# RcTransmitterSwitches.net
KiCad netlist of a schematic drawn in Altium Designer
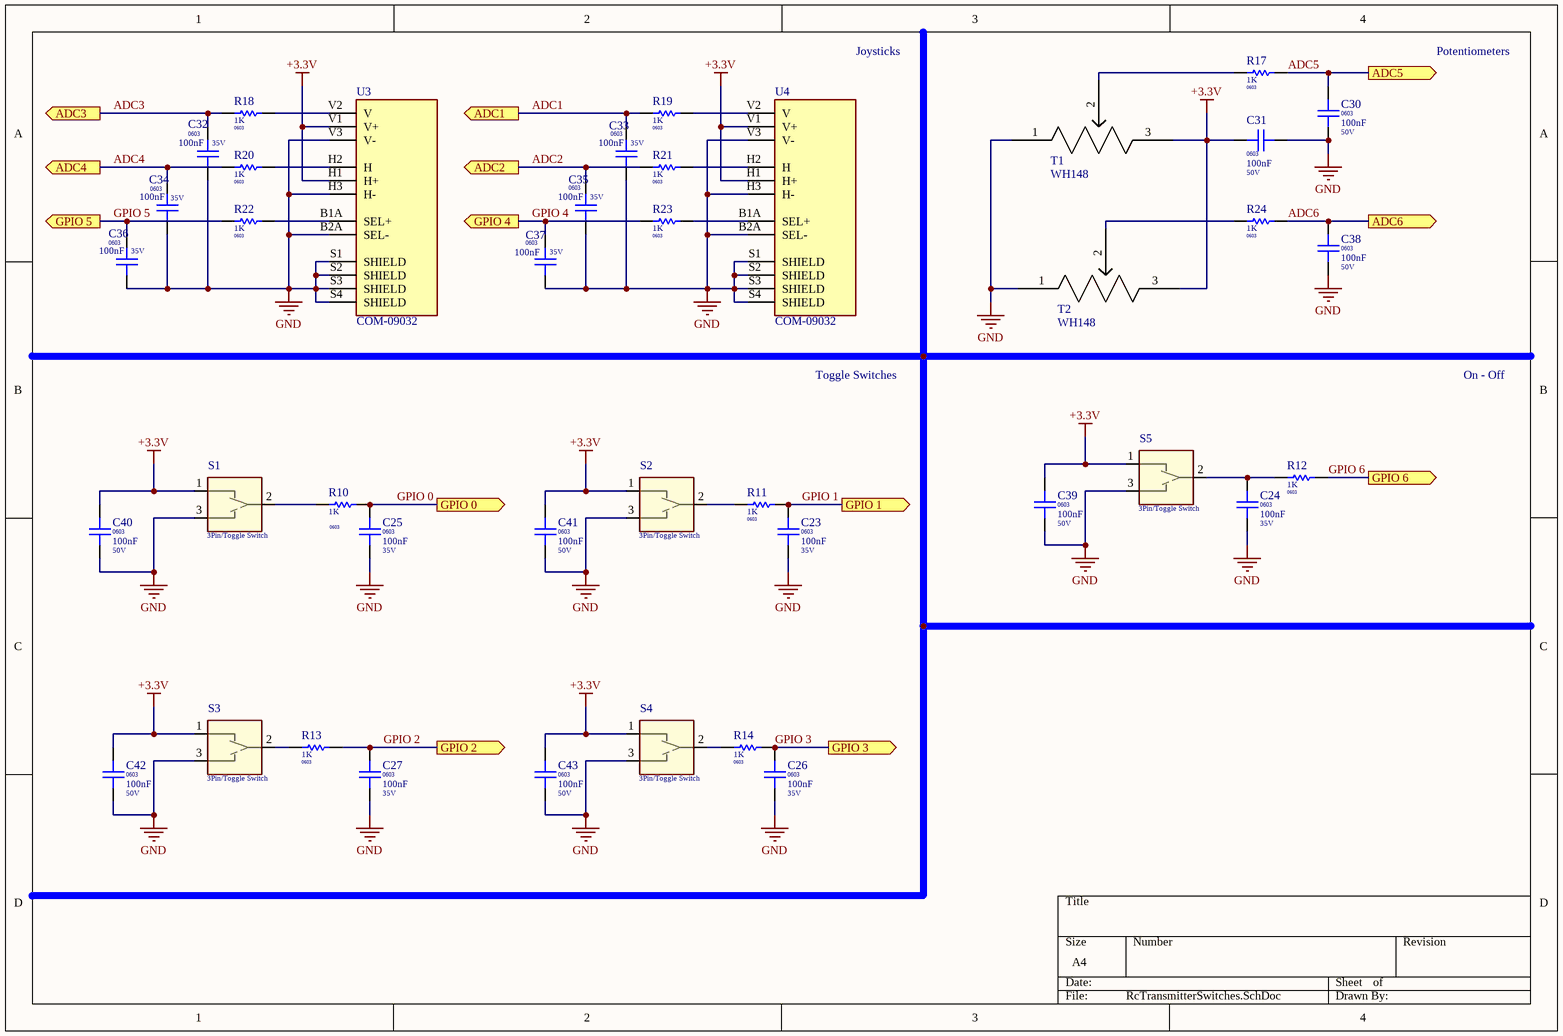
[diagram p0: RcTransmitterSwitches.SchDoc]

(export (version "E")
  (design (tool "Eeschema 10.0.6"))
  (components
    (comp (ref "C23")
      (value "100nF")
      (footprint "CAPC 0603")
      (description "Capacitor Ceramic 100nF 35V 0603")
      (fields
        (field (name "TOLERANCE") "%10")
        (field (name "PACKAGE / CASE") "0603")
        (field (name "VOLTAGE") "35V")
        (field (name "PART NUMBER") "CAPC0328")
      )
      (libsource (lib "AESK Database Library") (part "NPCapacitor"))
    )
    (comp (ref "C24")
      (value "100nF")
      (footprint "CAPC 0603")
      (description "Capacitor Ceramic 100nF 35V 0603")
      (fields
        (field (name "TOLERANCE") "%10")
        (field (name "PACKAGE / CASE") "0603")
        (field (name "VOLTAGE") "35V")
        (field (name "PART NUMBER") "CAPC0328")
      )
      (libsource (lib "AESK Database Library") (part "NPCapacitor"))
    )
    (comp (ref "C25")
      (value "100nF")
      (footprint "CAPC 0603")
      (description "Capacitor Ceramic 100nF 35V 0603")
      (fields
        (field (name "TOLERANCE") "%10")
        (field (name "PACKAGE / CASE") "0603")
        (field (name "VOLTAGE") "35V")
        (field (name "PART NUMBER") "CAPC0328")
      )
      (libsource (lib "AESK Database Library") (part "NPCapacitor"))
    )
    (comp (ref "C26")
      (value "100nF")
      (footprint "CAPC 0603")
      (description "Capacitor Ceramic 100nF 35V 0603")
      (fields
        (field (name "TOLERANCE") "%10")
        (field (name "PACKAGE / CASE") "0603")
        (field (name "VOLTAGE") "35V")
        (field (name "PART NUMBER") "CAPC0328")
      )
      (libsource (lib "AESK Database Library") (part "NPCapacitor"))
    )
    (comp (ref "C27")
      (value "100nF")
      (footprint "CAPC 0603")
      (description "Capacitor Ceramic 100nF 35V 0603")
      (fields
        (field (name "TOLERANCE") "%10")
        (field (name "PACKAGE / CASE") "0603")
        (field (name "VOLTAGE") "35V")
        (field (name "PART NUMBER") "CAPC0328")
      )
      (libsource (lib "AESK Database Library") (part "NPCapacitor"))
    )
    (comp (ref "C30")
      (value "100nF")
      (footprint "CAPC 0603")
      (description "Capacitor Ceramic 100nF 50V 0603")
      (fields
        (field (name "TOLERANCE") "%10")
        (field (name "PACKAGE / CASE") "0603")
        (field (name "VOLTAGE") "50V")
        (field (name "PART NUMBER") "CAPC0285")
      )
      (libsource (lib "AESK Database Library") (part "NPCapacitor"))
    )
    (comp (ref "C31")
      (value "100nF")
      (footprint "CAPC 0603")
      (description "Capacitor Ceramic 100nF 50V 0603")
      (fields
        (field (name "TOLERANCE") "%10")
        (field (name "PACKAGE / CASE") "0603")
        (field (name "VOLTAGE") "50V")
        (field (name "PART NUMBER") "CAPC0285")
      )
      (libsource (lib "AESK Database Library") (part "NPCapacitor"))
    )
    (comp (ref "C32")
      (value "100nF")
      (footprint "CAPC 0603")
      (description "Capacitor Ceramic 100nF 35V 0603")
      (fields
        (field (name "TOLERANCE") "%10")
        (field (name "PACKAGE / CASE") "0603")
        (field (name "VOLTAGE") "35V")
        (field (name "PART NUMBER") "CAPC0328")
      )
      (libsource (lib "AESK Database Library") (part "NPCapacitor"))
    )
    (comp (ref "C33")
      (value "100nF")
      (footprint "CAPC 0603")
      (description "Capacitor Ceramic 100nF 35V 0603")
      (fields
        (field (name "TOLERANCE") "%10")
        (field (name "PACKAGE / CASE") "0603")
        (field (name "VOLTAGE") "35V")
        (field (name "PART NUMBER") "CAPC0328")
      )
      (libsource (lib "AESK Database Library") (part "NPCapacitor"))
    )
    (comp (ref "C34")
      (value "100nF")
      (footprint "CAPC 0603")
      (description "Capacitor Ceramic 100nF 35V 0603")
      (fields
        (field (name "TOLERANCE") "%10")
        (field (name "PACKAGE / CASE") "0603")
        (field (name "VOLTAGE") "35V")
        (field (name "PART NUMBER") "CAPC0328")
      )
      (libsource (lib "AESK Database Library") (part "NPCapacitor"))
    )
    (comp (ref "C35")
      (value "100nF")
      (footprint "CAPC 0603")
      (description "Capacitor Ceramic 100nF 35V 0603")
      (fields
        (field (name "TOLERANCE") "%10")
        (field (name "PACKAGE / CASE") "0603")
        (field (name "VOLTAGE") "35V")
        (field (name "PART NUMBER") "CAPC0328")
      )
      (libsource (lib "AESK Database Library") (part "NPCapacitor"))
    )
    (comp (ref "C36")
      (value "100nF")
      (footprint "CAPC 0603")
      (description "Capacitor Ceramic 100nF 35V 0603")
      (fields
        (field (name "TOLERANCE") "%10")
        (field (name "PACKAGE / CASE") "0603")
        (field (name "VOLTAGE") "35V")
        (field (name "PART NUMBER") "CAPC0328")
      )
      (libsource (lib "AESK Database Library") (part "NPCapacitor"))
    )
    (comp (ref "C37")
      (value "100nF")
      (footprint "CAPC 0603")
      (description "Capacitor Ceramic 100nF 35V 0603")
      (fields
        (field (name "TOLERANCE") "%10")
        (field (name "PACKAGE / CASE") "0603")
        (field (name "VOLTAGE") "35V")
        (field (name "PART NUMBER") "CAPC0328")
      )
      (libsource (lib "AESK Database Library") (part "NPCapacitor"))
    )
    (comp (ref "C38")
      (value "100nF")
      (footprint "CAPC 0603")
      (description "Capacitor Ceramic 100nF 50V 0603")
      (fields
        (field (name "TOLERANCE") "%10")
        (field (name "PACKAGE / CASE") "0603")
        (field (name "VOLTAGE") "50V")
        (field (name "PART NUMBER") "CAPC0285")
      )
      (libsource (lib "AESK Database Library") (part "NPCapacitor"))
    )
    (comp (ref "C39")
      (value "100nF")
      (footprint "CAPC 0603")
      (description "Capacitor Ceramic 100nF 50V 0603")
      (fields
        (field (name "TOLERANCE") "%10")
        (field (name "PACKAGE / CASE") "0603")
        (field (name "VOLTAGE") "50V")
        (field (name "PART NUMBER") "CAPC0285")
      )
      (libsource (lib "AESK Database Library") (part "NPCapacitor"))
    )
    (comp (ref "C40")
      (value "100nF")
      (footprint "CAPC 0603")
      (description "Capacitor Ceramic 100nF 50V 0603")
      (fields
        (field (name "TOLERANCE") "%10")
        (field (name "PACKAGE / CASE") "0603")
        (field (name "VOLTAGE") "50V")
        (field (name "PART NUMBER") "CAPC0285")
      )
      (libsource (lib "AESK Database Library") (part "NPCapacitor"))
    )
    (comp (ref "C41")
      (value "100nF")
      (footprint "CAPC 0603")
      (description "Capacitor Ceramic 100nF 50V 0603")
      (fields
        (field (name "TOLERANCE") "%10")
        (field (name "PACKAGE / CASE") "0603")
        (field (name "VOLTAGE") "50V")
        (field (name "PART NUMBER") "CAPC0285")
      )
      (libsource (lib "AESK Database Library") (part "NPCapacitor"))
    )
    (comp (ref "C42")
      (value "100nF")
      (footprint "CAPC 0603")
      (description "Capacitor Ceramic 100nF 50V 0603")
      (fields
        (field (name "TOLERANCE") "%10")
        (field (name "PACKAGE / CASE") "0603")
        (field (name "VOLTAGE") "50V")
        (field (name "PART NUMBER") "CAPC0285")
      )
      (libsource (lib "AESK Database Library") (part "NPCapacitor"))
    )
    (comp (ref "C43")
      (value "100nF")
      (footprint "CAPC 0603")
      (description "Capacitor Ceramic 100nF 50V 0603")
      (fields
        (field (name "TOLERANCE") "%10")
        (field (name "PACKAGE / CASE") "0603")
        (field (name "VOLTAGE") "50V")
        (field (name "PART NUMBER") "CAPC0285")
      )
      (libsource (lib "AESK Database Library") (part "NPCapacitor"))
    )
    (comp (ref "R10")
      (value "1K")
      (footprint "RESC 0603")
      (description "1K 0603")
      (fields
        (field (name "TOLERANCE") "%5")
        (field (name "POWER") "1/10W")
        (field (name "PACKAGE / CASE") "0603")
      )
      (libsource (lib "AESK Database Library") (part "Resistor"))
    )
    (comp (ref "R11")
      (value "1K")
      (footprint "RESC 0603")
      (description "1K 0603")
      (fields
        (field (name "TOLERANCE") "%5")
        (field (name "POWER") "1/10W")
        (field (name "PACKAGE / CASE") "0603")
      )
      (libsource (lib "AESK Database Library") (part "Resistor"))
    )
    (comp (ref "R12")
      (value "1K")
      (footprint "RESC 0603")
      (description "1K 0603")
      (fields
        (field (name "TOLERANCE") "%5")
        (field (name "POWER") "1/10W")
        (field (name "PACKAGE / CASE") "0603")
      )
      (libsource (lib "AESK Database Library") (part "Resistor"))
    )
    (comp (ref "R13")
      (value "1K")
      (footprint "RESC 0603")
      (description "1K 0603")
      (fields
        (field (name "TOLERANCE") "%5")
        (field (name "POWER") "1/10W")
        (field (name "PACKAGE / CASE") "0603")
      )
      (libsource (lib "AESK Database Library") (part "Resistor"))
    )
    (comp (ref "R14")
      (value "1K")
      (footprint "RESC 0603")
      (description "1K 0603")
      (fields
        (field (name "TOLERANCE") "%5")
        (field (name "POWER") "1/10W")
        (field (name "PACKAGE / CASE") "0603")
      )
      (libsource (lib "AESK Database Library") (part "Resistor"))
    )
    (comp (ref "R17")
      (value "1K")
      (footprint "RESC 0603")
      (description "1K 0603")
      (fields
        (field (name "TOLERANCE") "%5")
        (field (name "POWER") "1/10W")
        (field (name "PACKAGE / CASE") "0603")
      )
      (libsource (lib "AESK Database Library") (part "Resistor"))
    )
    (comp (ref "R18")
      (value "1K")
      (footprint "RESC 0603")
      (description "1K 0603")
      (fields
        (field (name "TOLERANCE") "%5")
        (field (name "POWER") "1/10W")
        (field (name "PACKAGE / CASE") "0603")
      )
      (libsource (lib "AESK Database Library") (part "Resistor"))
    )
    (comp (ref "R19")
      (value "1K")
      (footprint "RESC 0603")
      (description "1K 0603")
      (fields
        (field (name "TOLERANCE") "%5")
        (field (name "POWER") "1/10W")
        (field (name "PACKAGE / CASE") "0603")
      )
      (libsource (lib "AESK Database Library") (part "Resistor"))
    )
    (comp (ref "R20")
      (value "1K")
      (footprint "RESC 0603")
      (description "1K 0603")
      (fields
        (field (name "TOLERANCE") "%5")
        (field (name "POWER") "1/10W")
        (field (name "PACKAGE / CASE") "0603")
      )
      (libsource (lib "AESK Database Library") (part "Resistor"))
    )
    (comp (ref "R21")
      (value "1K")
      (footprint "RESC 0603")
      (description "1K 0603")
      (fields
        (field (name "TOLERANCE") "%5")
        (field (name "POWER") "1/10W")
        (field (name "PACKAGE / CASE") "0603")
      )
      (libsource (lib "AESK Database Library") (part "Resistor"))
    )
    (comp (ref "R22")
      (value "1K")
      (footprint "RESC 0603")
      (description "1K 0603")
      (fields
        (field (name "TOLERANCE") "%5")
        (field (name "POWER") "1/10W")
        (field (name "PACKAGE / CASE") "0603")
      )
      (libsource (lib "AESK Database Library") (part "Resistor"))
    )
    (comp (ref "R23")
      (value "1K")
      (footprint "RESC 0603")
      (description "1K 0603")
      (fields
        (field (name "TOLERANCE") "%5")
        (field (name "POWER") "1/10W")
        (field (name "PACKAGE / CASE") "0603")
      )
      (libsource (lib "AESK Database Library") (part "Resistor"))
    )
    (comp (ref "R24")
      (value "1K")
      (footprint "RESC 0603")
      (description "1K 0603")
      (fields
        (field (name "TOLERANCE") "%5")
        (field (name "POWER") "1/10W")
        (field (name "PACKAGE / CASE") "0603")
      )
      (libsource (lib "AESK Database Library") (part "Resistor"))
    )
    (comp (ref "S1")
      (value "3Pin/Toggle Switch")
      (footprint "3Pin/Toggle Switch")
      (description "Switch Toggle ON None ON SPDT Long Baton Lever PC Pins 5A 250VAC 28VDC PC Mount with Threads Bulk")
      (fields
        (field (name "MF") "TE Connectivity")
        (field (name "MP") "4-1825136-5")
        (field (name "NAME") "3Pin/Toggle Switch")
      )
      (libsource (lib "RcTransmitterSchlib1") (part "4-1825136-5"))
    )
    (comp (ref "S2")
      (value "3Pin/Toggle Switch")
      (footprint "3Pin/Toggle Switch")
      (description "Switch Toggle ON None ON SPDT Long Baton Lever PC Pins 5A 250VAC 28VDC PC Mount with Threads Bulk")
      (fields
        (field (name "MF") "TE Connectivity")
        (field (name "MP") "4-1825136-5")
        (field (name "NAME") "3Pin/Toggle Switch")
      )
      (libsource (lib "RcTransmitterSchlib1") (part "4-1825136-5"))
    )
    (comp (ref "S3")
      (value "3Pin/Toggle Switch")
      (footprint "3Pin/Toggle Switch")
      (description "Switch Toggle ON None ON SPDT Long Baton Lever PC Pins 5A 250VAC 28VDC PC Mount with Threads Bulk")
      (fields
        (field (name "MF") "TE Connectivity")
        (field (name "MP") "4-1825136-5")
        (field (name "NAME") "3Pin/Toggle Switch")
      )
      (libsource (lib "RcTransmitterSchlib1") (part "4-1825136-5"))
    )
    (comp (ref "S4")
      (value "3Pin/Toggle Switch")
      (footprint "3Pin/Toggle Switch")
      (description "Switch Toggle ON None ON SPDT Long Baton Lever PC Pins 5A 250VAC 28VDC PC Mount with Threads Bulk")
      (fields
        (field (name "MF") "TE Connectivity")
        (field (name "MP") "4-1825136-5")
        (field (name "NAME") "3Pin/Toggle Switch")
      )
      (libsource (lib "RcTransmitterSchlib1") (part "4-1825136-5"))
    )
    (comp (ref "S5")
      (value "3Pin/Toggle Switch")
      (footprint "3Pin/Toggle Switch")
      (description "Switch Toggle ON None ON SPDT Long Baton Lever PC Pins 5A 250VAC 28VDC PC Mount with Threads Bulk")
      (fields
        (field (name "MF") "TE Connectivity")
        (field (name "MP") "4-1825136-5")
        (field (name "NAME") "3Pin/Toggle Switch")
      )
      (libsource (lib "RcTransmitterSchlib1") (part "4-1825136-5"))
    )
    (comp (ref "T1")
      (value "WH148")
      (footprint "WH148")
      (libsource (lib "RcTransmitterSchlib1") (part "WH148"))
    )
    (comp (ref "T2")
      (value "WH148")
      (footprint "WH148")
      (libsource (lib "RcTransmitterSchlib1") (part "WH148"))
    )
    (comp (ref "U3")
      (value "COM-09032")
      (footprint "XDCR_COM-09032")
      (description "Joystick, 2 - Axis Analog _Resistive_ Output")
      (fields (field (name "MF") "SparkFun Electronics"))
      (libsource (lib "RcTransmitterSchlib1") (part "COM-09032"))
    )
    (comp (ref "U4")
      (value "COM-09032")
      (footprint "XDCR_COM-09032")
      (description "Joystick, 2 - Axis Analog _Resistive_ Output")
      (fields (field (name "MF") "SparkFun Electronics"))
      (libsource (lib "RcTransmitterSchlib1") (part "COM-09032"))
    )
  )
  (nets
    (net (code "1") (name "+3.3V") (class "Default")
      (node (ref "C31") (pin "2") (pinfunction "2_2") (pintype "passive"))
      (node (ref "C39") (pin "2") (pinfunction "2_2") (pintype "passive"))
      (node (ref "C40") (pin "2") (pinfunction "2_2") (pintype "passive"))
      (node (ref "C41") (pin "2") (pinfunction "2_2") (pintype "passive"))
      (node (ref "C42") (pin "2") (pinfunction "2_2") (pintype "passive"))
      (node (ref "C43") (pin "2") (pinfunction "2_2") (pintype "passive"))
      (node (ref "S1") (pin "1") (pinfunction "1_1") (pintype "passive"))
      (node (ref "S2") (pin "1") (pinfunction "1_1") (pintype "passive"))
      (node (ref "S3") (pin "1") (pinfunction "1_1") (pintype "passive"))
      (node (ref "S4") (pin "1") (pinfunction "1_1") (pintype "passive"))
      (node (ref "S5") (pin "1") (pinfunction "1_1") (pintype "passive"))
      (node (ref "T1") (pin "3") (pintype "passive"))
      (node (ref "T2") (pin "3") (pintype "passive"))
      (node (ref "U3") (pin "H1") (pinfunction "H+_H1") (pintype "passive"))
      (node (ref "U3") (pin "V1") (pinfunction "V+_V1") (pintype "passive"))
      (node (ref "U4") (pin "H1") (pinfunction "H+_H1") (pintype "passive"))
      (node (ref "U4") (pin "V1") (pinfunction "V+_V1") (pintype "passive"))
    )
    (net (code "2") (name "/ADC1") (class "Default")
      (node (ref "C33") (pin "2") (pinfunction "2_2") (pintype "passive"))
      (node (ref "R19") (pin "1") (pinfunction "1_1") (pintype "passive"))
    )
    (net (code "3") (name "/ADC2") (class "Default")
      (node (ref "C35") (pin "2") (pinfunction "2_2") (pintype "passive"))
      (node (ref "R21") (pin "1") (pinfunction "1_1") (pintype "passive"))
    )
    (net (code "4") (name "/ADC3") (class "Default")
      (node (ref "C32") (pin "2") (pinfunction "2_2") (pintype "passive"))
      (node (ref "R18") (pin "1") (pinfunction "1_1") (pintype "passive"))
    )
    (net (code "5") (name "/ADC4") (class "Default")
      (node (ref "C34") (pin "2") (pinfunction "2_2") (pintype "passive"))
      (node (ref "R20") (pin "1") (pinfunction "1_1") (pintype "passive"))
    )
    (net (code "6") (name "/ADC5") (class "Default")
      (node (ref "C30") (pin "1") (pinfunction "1_1") (pintype "passive"))
      (node (ref "R17") (pin "2") (pinfunction "2_2") (pintype "passive"))
    )
    (net (code "7") (name "/ADC6") (class "Default")
      (node (ref "C38") (pin "1") (pinfunction "1_1") (pintype "passive"))
      (node (ref "R24") (pin "2") (pinfunction "2_2") (pintype "passive"))
    )
    (net (code "8") (name "/GPIO 0") (class "Default")
      (node (ref "C25") (pin "2") (pinfunction "2_2") (pintype "passive"))
      (node (ref "R10") (pin "2") (pinfunction "2_2") (pintype "passive"))
    )
    (net (code "9") (name "/GPIO 1") (class "Default")
      (node (ref "C23") (pin "2") (pinfunction "2_2") (pintype "passive"))
      (node (ref "R11") (pin "2") (pinfunction "2_2") (pintype "passive"))
    )
    (net (code "10") (name "/GPIO 2") (class "Default")
      (node (ref "C27") (pin "2") (pinfunction "2_2") (pintype "passive"))
      (node (ref "R13") (pin "2") (pinfunction "2_2") (pintype "passive"))
    )
    (net (code "11") (name "/GPIO 3") (class "Default")
      (node (ref "C26") (pin "2") (pinfunction "2_2") (pintype "passive"))
      (node (ref "R14") (pin "1") (pinfunction "1_1") (pintype "passive"))
    )
    (net (code "12") (name "/GPIO 4") (class "Default")
      (node (ref "C37") (pin "2") (pinfunction "2_2") (pintype "passive"))
      (node (ref "R23") (pin "1") (pinfunction "1_1") (pintype "passive"))
    )
    (net (code "13") (name "/GPIO 5") (class "Default")
      (node (ref "C36") (pin "2") (pinfunction "2_2") (pintype "passive"))
      (node (ref "R22") (pin "1") (pinfunction "1_1") (pintype "passive"))
    )
    (net (code "14") (name "/GPIO 6") (class "Default")
      (node (ref "R12") (pin "2") (pinfunction "2_2") (pintype "passive"))
    )
    (net (code "15") (name "GND") (class "Default")
      (node (ref "C23") (pin "1") (pinfunction "1_1") (pintype "passive"))
      (node (ref "C24") (pin "1") (pinfunction "1_1") (pintype "passive"))
      (node (ref "C25") (pin "1") (pinfunction "1_1") (pintype "passive"))
      (node (ref "C26") (pin "1") (pinfunction "1_1") (pintype "passive"))
      (node (ref "C27") (pin "1") (pinfunction "1_1") (pintype "passive"))
      (node (ref "C30") (pin "2") (pinfunction "2_2") (pintype "passive"))
      (node (ref "C31") (pin "1") (pinfunction "1_1") (pintype "passive"))
      (node (ref "C32") (pin "1") (pinfunction "1_1") (pintype "passive"))
      (node (ref "C33") (pin "1") (pinfunction "1_1") (pintype "passive"))
      (node (ref "C34") (pin "1") (pinfunction "1_1") (pintype "passive"))
      (node (ref "C35") (pin "1") (pinfunction "1_1") (pintype "passive"))
      (node (ref "C36") (pin "1") (pinfunction "1_1") (pintype "passive"))
      (node (ref "C37") (pin "1") (pinfunction "1_1") (pintype "passive"))
      (node (ref "C38") (pin "2") (pinfunction "2_2") (pintype "passive"))
      (node (ref "C39") (pin "1") (pinfunction "1_1") (pintype "passive"))
      (node (ref "C40") (pin "1") (pinfunction "1_1") (pintype "passive"))
      (node (ref "C41") (pin "1") (pinfunction "1_1") (pintype "passive"))
      (node (ref "C42") (pin "1") (pinfunction "1_1") (pintype "passive"))
      (node (ref "C43") (pin "1") (pinfunction "1_1") (pintype "passive"))
      (node (ref "S1") (pin "3") (pinfunction "3_3") (pintype "passive"))
      (node (ref "S2") (pin "3") (pinfunction "3_3") (pintype "passive"))
      (node (ref "S3") (pin "3") (pinfunction "3_3") (pintype "passive"))
      (node (ref "S4") (pin "3") (pinfunction "3_3") (pintype "passive"))
      (node (ref "S5") (pin "3") (pinfunction "3_3") (pintype "passive"))
      (node (ref "T1") (pin "1") (pintype "passive"))
      (node (ref "T2") (pin "1") (pintype "passive"))
      (node (ref "U3") (pin "B2A") (pinfunction "SEL-_B2A") (pintype "passive"))
      (node (ref "U3") (pin "H3") (pinfunction "H-_H3") (pintype "passive"))
      (node (ref "U3") (pin "S1") (pinfunction "SHIELD_S1") (pintype "passive"))
      (node (ref "U3") (pin "S2") (pinfunction "SHIELD_S2") (pintype "passive"))
      (node (ref "U3") (pin "S3") (pinfunction "SHIELD_S3") (pintype "passive"))
      (node (ref "U3") (pin "S4") (pinfunction "SHIELD_S4") (pintype "passive"))
      (node (ref "U3") (pin "V3") (pinfunction "V-_V3") (pintype "passive"))
      (node (ref "U4") (pin "B2A") (pinfunction "SEL-_B2A") (pintype "passive"))
      (node (ref "U4") (pin "H3") (pinfunction "H-_H3") (pintype "passive"))
      (node (ref "U4") (pin "S1") (pinfunction "SHIELD_S1") (pintype "passive"))
      (node (ref "U4") (pin "S2") (pinfunction "SHIELD_S2") (pintype "passive"))
      (node (ref "U4") (pin "S3") (pinfunction "SHIELD_S3") (pintype "passive"))
      (node (ref "U4") (pin "S4") (pinfunction "SHIELD_S4") (pintype "passive"))
      (node (ref "U4") (pin "V3") (pinfunction "V-_V3") (pintype "passive"))
    )
    (net (code "16") (name "Net-(C24-Pad2)") (class "Default")
      (node (ref "C24") (pin "2") (pinfunction "2_2") (pintype "passive"))
      (node (ref "R12") (pin "1") (pinfunction "1_1") (pintype "passive"))
      (node (ref "S5") (pin "2") (pinfunction "2_2") (pintype "passive"))
    )
    (net (code "17") (name "Net-(R10-Pad1)") (class "Default")
      (node (ref "R10") (pin "1") (pinfunction "1_1") (pintype "passive"))
      (node (ref "S1") (pin "2") (pinfunction "2_2") (pintype "passive"))
    )
    (net (code "18") (name "Net-(R11-Pad1)") (class "Default")
      (node (ref "R11") (pin "1") (pinfunction "1_1") (pintype "passive"))
      (node (ref "S2") (pin "2") (pinfunction "2_2") (pintype "passive"))
    )
    (net (code "19") (name "Net-(R13-Pad1)") (class "Default")
      (node (ref "R13") (pin "1") (pinfunction "1_1") (pintype "passive"))
      (node (ref "S3") (pin "2") (pinfunction "2_2") (pintype "passive"))
    )
    (net (code "20") (name "Net-(R14-Pad2)") (class "Default")
      (node (ref "R14") (pin "2") (pinfunction "2_2") (pintype "passive"))
      (node (ref "S4") (pin "2") (pinfunction "2_2") (pintype "passive"))
    )
    (net (code "21") (name "Net-(R17-Pad1)") (class "Default")
      (node (ref "R17") (pin "1") (pinfunction "1_1") (pintype "passive"))
      (node (ref "T1") (pin "2") (pintype "passive"))
    )
    (net (code "22") (name "Net-(R24-Pad1)") (class "Default")
      (node (ref "R24") (pin "1") (pinfunction "1_1") (pintype "passive"))
      (node (ref "T2") (pin "2") (pintype "passive"))
    )
    (net (code "23") (name "Net-(U3-H)") (class "Default")
      (node (ref "R20") (pin "2") (pinfunction "2_2") (pintype "passive"))
      (node (ref "U3") (pin "H2") (pinfunction "H_H2") (pintype "passive"))
    )
    (net (code "24") (name "Net-(U3-SEL+)") (class "Default")
      (node (ref "R22") (pin "2") (pinfunction "2_2") (pintype "passive"))
      (node (ref "U3") (pin "B1A") (pinfunction "SEL+_B1A") (pintype "passive"))
    )
    (net (code "25") (name "Net-(U3-V)") (class "Default")
      (node (ref "R18") (pin "2") (pinfunction "2_2") (pintype "passive"))
      (node (ref "U3") (pin "V2") (pinfunction "V_V2") (pintype "passive"))
    )
    (net (code "26") (name "Net-(U4-H)") (class "Default")
      (node (ref "R21") (pin "2") (pinfunction "2_2") (pintype "passive"))
      (node (ref "U4") (pin "H2") (pinfunction "H_H2") (pintype "passive"))
    )
    (net (code "27") (name "Net-(U4-SEL+)") (class "Default")
      (node (ref "R23") (pin "2") (pinfunction "2_2") (pintype "passive"))
      (node (ref "U4") (pin "B1A") (pinfunction "SEL+_B1A") (pintype "passive"))
    )
    (net (code "28") (name "Net-(U4-V)") (class "Default")
      (node (ref "R19") (pin "2") (pinfunction "2_2") (pintype "passive"))
      (node (ref "U4") (pin "V2") (pinfunction "V_V2") (pintype "passive"))
    )
  )
)
